# C210_0003_SARA_Module_220601.net
KiCad netlist of a schematic drawn in Altium Designer
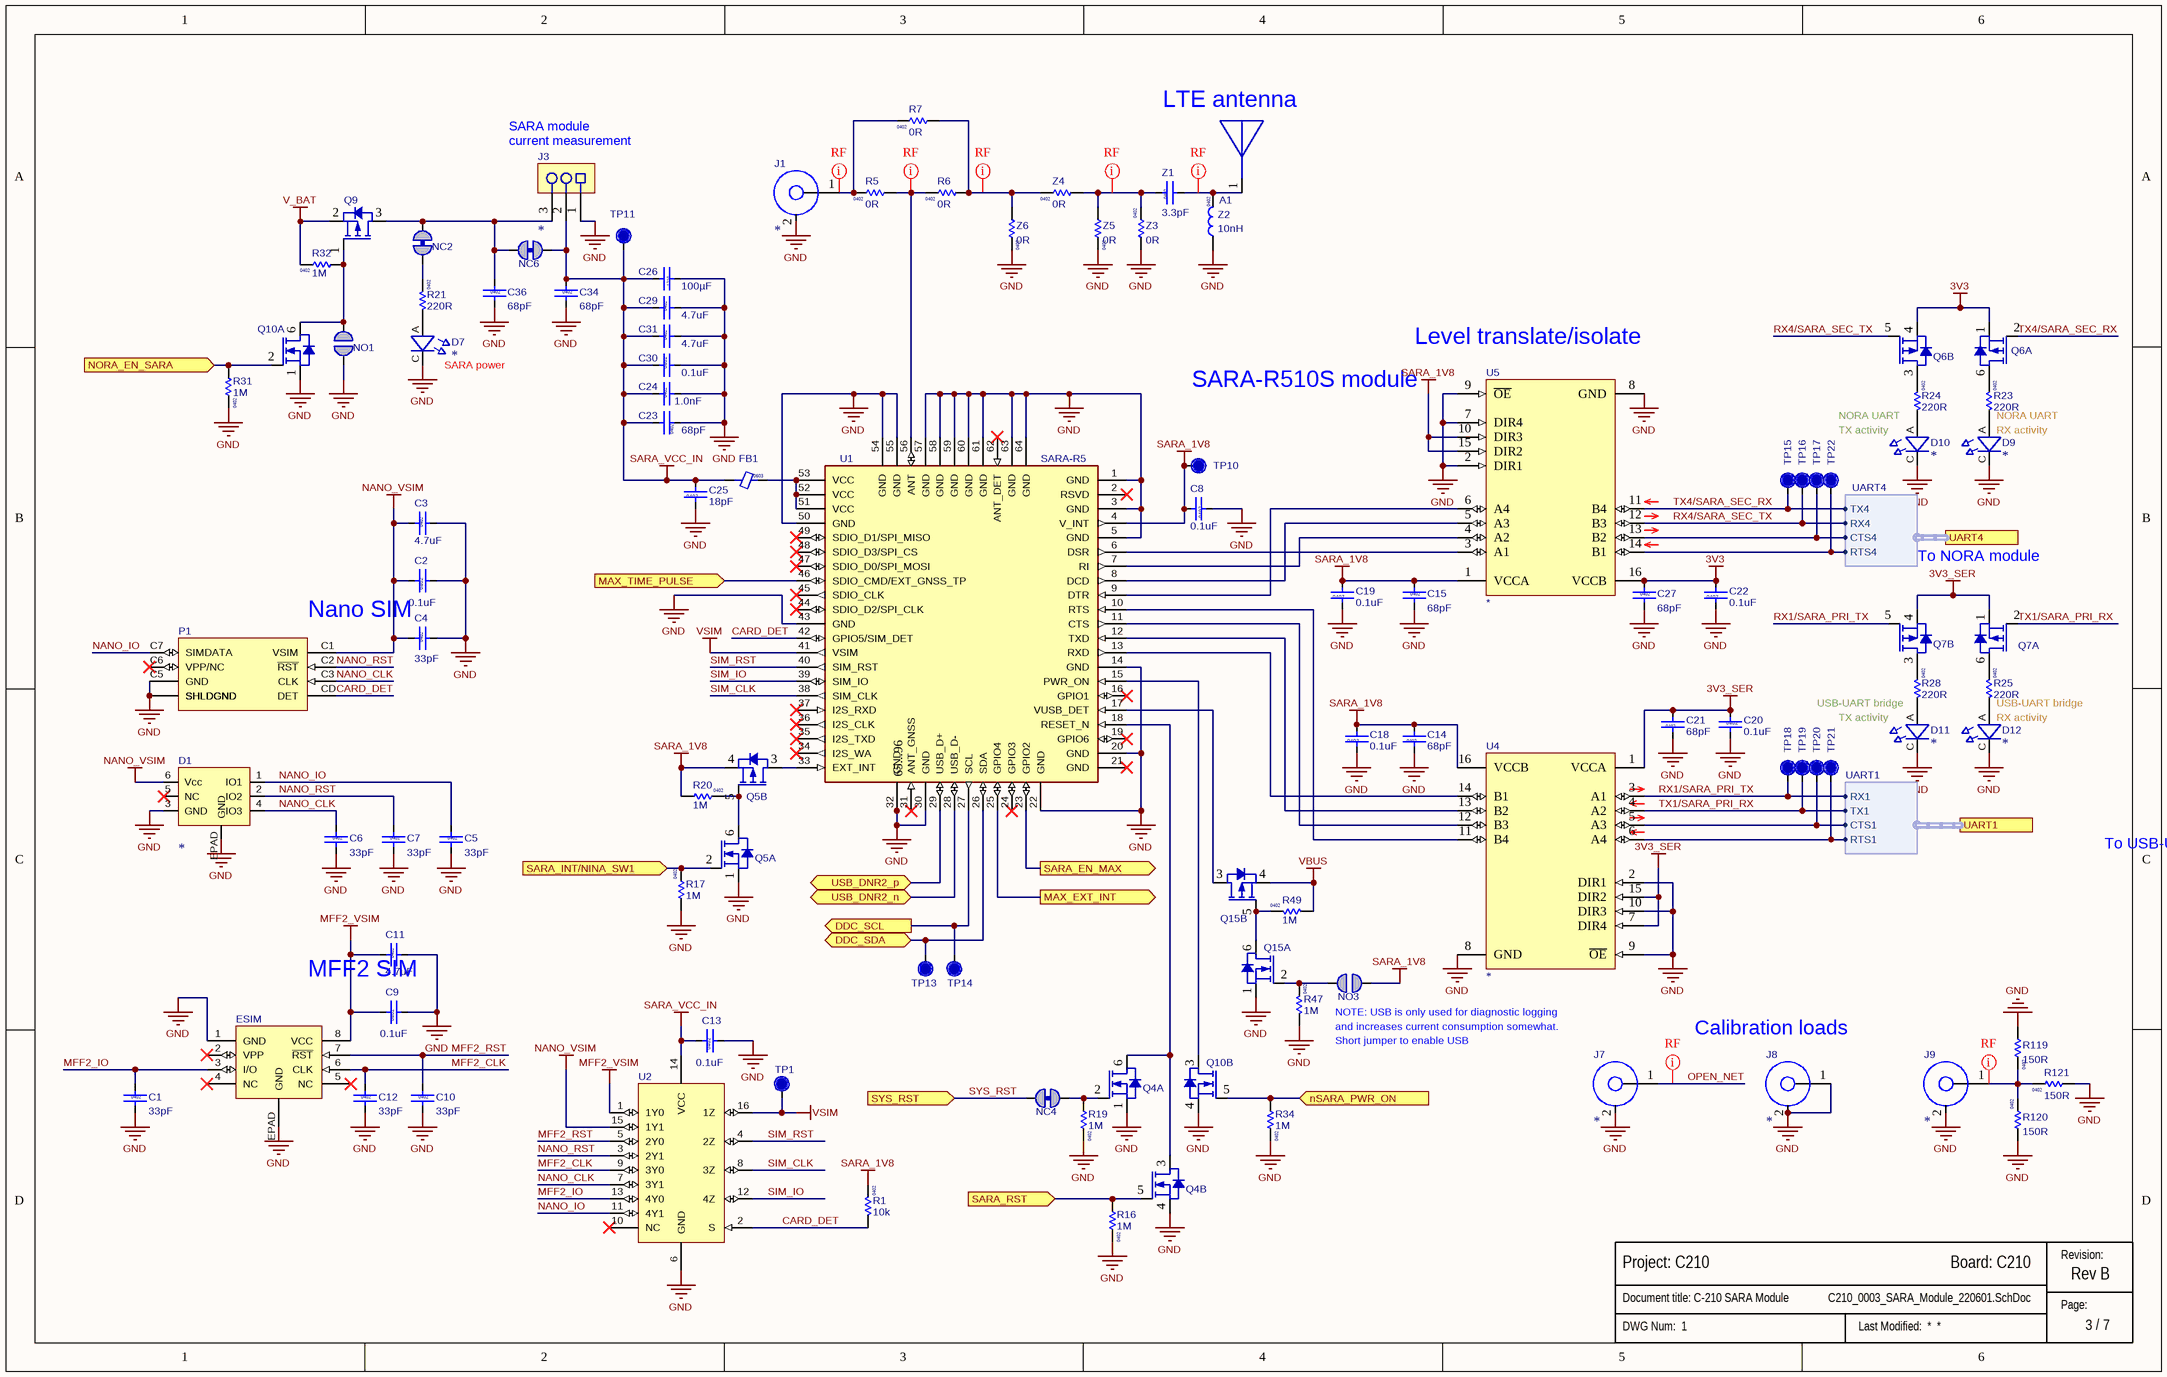
[diagram p0: C210_0003_SARA_Module_220601.SchDoc]

(export (version "E")
  (design (tool "Eeschema 10.0.6"))
  (components
    (comp (ref "A1")
      (value "PCS.66.A")
      (footprint "PCS_66_A")
      (description "RF Passive, Antenna, LTE, 600-6000MHz, Monopole")
      (fields (field (name "VOLTAGE") "None"))
      (libsource (lib "C210 Rev_B_220601") (part "PCS.66.A"))
    )
    (comp (ref "C1")
      (value "33pF")
      (footprint "Cap 0402 HD")
      (description "Cap, Ceramic,  33pF, 50V, 5%, NPO, 0402")
      (fields
        (field (name "SIZE") "0402")
        (field (name "PART NUMBER") "120-00045")
        (field (name "TOLERANCE") "+/- 5%")
      )
      (libsource (lib "Arena_Parts_DB_Lib") (part "Cap Chip"))
    )
    (comp (ref "C2")
      (value "0.1uF")
      (footprint "Cap 0402 HD")
      (description "Cap, Ceramic 0.1uF 10V 10% X5R 0402")
      (fields
        (field (name "SIZE") "0402")
        (field (name "PART NUMBER") "120-00016")
        (field (name "MANUFACTURER") "Murata Electronics North America")
      )
      (libsource (lib "Arena_Parts_DB_Lib") (part "Cap Chip"))
    )
    (comp (ref "C3")
      (value "4.7uF")
      (footprint "Cap 0402 HD")
      (description "Cap, Ceramic 4.7uF 10V 20% X5R 0402")
      (fields
        (field (name "SIZE") "0402")
        (field (name "PART NUMBER") "120-00020")
        (field (name "TOLERANCE") "+/- 20%")
      )
      (libsource (lib "Arena_Parts_DB_Lib") (part "Cap Chip"))
    )
    (comp (ref "C4")
      (value "33pF")
      (footprint "Cap 0402 HD")
      (description "Cap, Ceramic,  33pF, 50V, 5%, NPO, 0402")
      (fields
        (field (name "SIZE") "0402")
        (field (name "PART NUMBER") "120-00045")
        (field (name "TOLERANCE") "+/- 5%")
      )
      (libsource (lib "Arena_Parts_DB_Lib") (part "Cap Chip"))
    )
    (comp (ref "C5")
      (value "33pF")
      (footprint "Cap 0402 HD")
      (description "Cap, Ceramic,  33pF, 50V, 5%, NPO, 0402")
      (fields
        (field (name "SIZE") "0402")
        (field (name "PART NUMBER") "120-00045")
        (field (name "TOLERANCE") "+/- 5%")
      )
      (libsource (lib "Arena_Parts_DB_Lib") (part "Cap Chip"))
    )
    (comp (ref "C6")
      (value "33pF")
      (footprint "Cap 0402 HD")
      (description "Cap, Ceramic,  33pF, 50V, 5%, NPO, 0402")
      (fields
        (field (name "SIZE") "0402")
        (field (name "PART NUMBER") "120-00045")
        (field (name "TOLERANCE") "+/- 5%")
      )
      (libsource (lib "Arena_Parts_DB_Lib") (part "Cap Chip"))
    )
    (comp (ref "C7")
      (value "33pF")
      (footprint "Cap 0402 HD")
      (description "Cap, Ceramic,  33pF, 50V, 5%, NPO, 0402")
      (fields
        (field (name "SIZE") "0402")
        (field (name "PART NUMBER") "120-00045")
        (field (name "TOLERANCE") "+/- 5%")
      )
      (libsource (lib "Arena_Parts_DB_Lib") (part "Cap Chip"))
    )
    (comp (ref "C8")
      (value "0.1uF")
      (footprint "Cap 0402 HD")
      (description "Cap, Ceramic 0.1uF 10V 10% X5R 0402")
      (fields
        (field (name "SIZE") "0402")
        (field (name "PART NUMBER") "120-00016")
        (field (name "MANUFACTURER") "Murata Electronics North America")
      )
      (libsource (lib "Arena_Parts_DB_Lib") (part "Cap Chip"))
    )
    (comp (ref "C9")
      (value "0.1uF")
      (footprint "Cap 0402 HD")
      (description "Cap, Ceramic 0.1uF 10V 10% X5R 0402")
      (fields
        (field (name "SIZE") "0402")
        (field (name "PART NUMBER") "120-00016")
        (field (name "MANUFACTURER") "Murata Electronics North America")
      )
      (libsource (lib "Arena_Parts_DB_Lib") (part "Cap Chip"))
    )
    (comp (ref "C10")
      (value "33pF")
      (footprint "Cap 0402 HD")
      (description "Cap, Ceramic,  33pF, 50V, 5%, NPO, 0402")
      (fields
        (field (name "SIZE") "0402")
        (field (name "PART NUMBER") "120-00045")
        (field (name "TOLERANCE") "+/- 5%")
      )
      (libsource (lib "Arena_Parts_DB_Lib") (part "Cap Chip"))
    )
    (comp (ref "C11")
      (value "4.7uF")
      (footprint "Cap 0402 HD")
      (description "Cap, Ceramic 4.7uF 10V 20% X5R 0402")
      (fields
        (field (name "SIZE") "0402")
        (field (name "PART NUMBER") "120-00020")
        (field (name "TOLERANCE") "+/- 20%")
      )
      (libsource (lib "Arena_Parts_DB_Lib") (part "Cap Chip"))
    )
    (comp (ref "C12")
      (value "33pF")
      (footprint "Cap 0402 HD")
      (description "Cap, Ceramic,  33pF, 50V, 5%, NPO, 0402")
      (fields
        (field (name "SIZE") "0402")
        (field (name "PART NUMBER") "120-00045")
        (field (name "TOLERANCE") "+/- 5%")
      )
      (libsource (lib "Arena_Parts_DB_Lib") (part "Cap Chip"))
    )
    (comp (ref "C13")
      (value "0.1uF")
      (footprint "Cap 0402 HD")
      (description "Cap, Ceramic 0.1uF 10V 10% X5R 0402")
      (fields
        (field (name "SIZE") "0402")
        (field (name "PART NUMBER") "120-00016")
        (field (name "MANUFACTURER") "Murata Electronics North America")
      )
      (libsource (lib "Arena_Parts_DB_Lib") (part "Cap Chip"))
    )
    (comp (ref "C14")
      (value "68pF")
      (footprint "Cap 0402 HD")
      (description "Cap, Ceramic, 68pF, 50V, 1%, NP0, 0402")
      (fields
        (field (name "SIZE") "0402")
        (field (name "PART NUMBER") "120-00047")
        (field (name "TOLERANCE") "+/- 1%")
      )
      (libsource (lib "Arena_Parts_DB_Lib") (part "Cap Chip"))
    )
    (comp (ref "C15")
      (value "68pF")
      (footprint "Cap 0402 HD")
      (description "Cap, Ceramic, 68pF, 50V, 1%, NP0, 0402")
      (fields
        (field (name "SIZE") "0402")
        (field (name "PART NUMBER") "120-00047")
        (field (name "TOLERANCE") "+/- 1%")
      )
      (libsource (lib "Arena_Parts_DB_Lib") (part "Cap Chip"))
    )
    (comp (ref "C18")
      (value "0.1uF")
      (footprint "Cap 0402 HD")
      (description "Cap, Ceramic 0.1uF 10V 10% X5R 0402")
      (fields
        (field (name "SIZE") "0402")
        (field (name "PART NUMBER") "120-00016")
        (field (name "MANUFACTURER") "Murata Electronics North America")
      )
      (libsource (lib "Arena_Parts_DB_Lib") (part "Cap Chip"))
    )
    (comp (ref "C19")
      (value "0.1uF")
      (footprint "Cap 0402 HD")
      (description "Cap, Ceramic 0.1uF 10V 10% X5R 0402")
      (fields
        (field (name "SIZE") "0402")
        (field (name "PART NUMBER") "120-00016")
        (field (name "MANUFACTURER") "Murata Electronics North America")
      )
      (libsource (lib "Arena_Parts_DB_Lib") (part "Cap Chip"))
    )
    (comp (ref "C20")
      (value "0.1uF")
      (footprint "Cap 0402 HD")
      (description "Cap, Ceramic 0.1uF 10V 10% X5R 0402")
      (fields
        (field (name "SIZE") "0402")
        (field (name "PART NUMBER") "120-00016")
        (field (name "MANUFACTURER") "Murata Electronics North America")
      )
      (libsource (lib "Arena_Parts_DB_Lib") (part "Cap Chip"))
    )
    (comp (ref "C21")
      (value "68pF")
      (footprint "Cap 0402 HD")
      (description "Cap, Ceramic, 68pF, 50V, 1%, NP0, 0402")
      (fields
        (field (name "SIZE") "0402")
        (field (name "PART NUMBER") "120-00047")
        (field (name "TOLERANCE") "+/- 1%")
      )
      (libsource (lib "Arena_Parts_DB_Lib") (part "Cap Chip"))
    )
    (comp (ref "C22")
      (value "0.1uF")
      (footprint "Cap 0402 HD")
      (description "Cap, Ceramic 0.1uF 10V 10% X5R 0402")
      (fields
        (field (name "SIZE") "0402")
        (field (name "PART NUMBER") "120-00016")
        (field (name "MANUFACTURER") "Murata Electronics North America")
      )
      (libsource (lib "Arena_Parts_DB_Lib") (part "Cap Chip"))
    )
    (comp (ref "C23")
      (value "68pF")
      (footprint "Cap 0402 HD")
      (description "Cap, Ceramic, 68pF, 50V, 1%, NP0, 0402")
      (fields
        (field (name "SIZE") "0402")
        (field (name "PART NUMBER") "120-00047")
        (field (name "TOLERANCE") "+/- 1%")
      )
      (libsource (lib "Arena_Parts_DB_Lib") (part "Cap Chip"))
    )
    (comp (ref "C24")
      (value "1.0nF")
      (footprint "Cap 0402 HD")
      (description "CAP CER 1.0nF 50V 10% X7R 0402")
      (fields
        (field (name "SIZE") "0402")
        (field (name "PART NUMBER") "120-00010")
        (field (name "TOLERANCE") "+/- 10%")
      )
      (libsource (lib "Arena_Parts_DB_Lib") (part "Cap Chip"))
    )
    (comp (ref "C25")
      (value "18pF")
      (footprint "Cap 0402 HD")
      (description "Cap, Ceramic 18pF 50V 5% NP0 0402")
      (fields
        (field (name "SIZE") "0402")
        (field (name "PART NUMBER") "120-00041")
        (field (name "TOLERANCE") "+/- 5%")
      )
      (libsource (lib "Arena_Parts_DB_Lib") (part "Cap Chip"))
    )
    (comp (ref "C26")
      (value "100µF")
      (footprint "Cap 1210")
      (description "100µF ±20% 10V Ceramic Capacitor X5R 1210 (3225 Metric)")
      (fields
        (field (name "SIZE") "1210")
        (field (name "PART NUMBER") "120-00223")
        (field (name "TOLERANCE") "+/- 20%")
      )
      (libsource (lib "Arena_Parts_DB_Lib") (part "Cap Chip"))
    )
    (comp (ref "C27")
      (value "68pF")
      (footprint "Cap 0402 HD")
      (description "Cap, Ceramic, 68pF, 50V, 1%, NP0, 0402")
      (fields
        (field (name "SIZE") "0402")
        (field (name "PART NUMBER") "120-00047")
        (field (name "TOLERANCE") "+/- 1%")
      )
      (libsource (lib "Arena_Parts_DB_Lib") (part "Cap Chip"))
    )
    (comp (ref "C29")
      (value "4.7uF")
      (footprint "Cap 0402 HD")
      (description "Cap, Ceramic 4.7uF 10V 20% X5R 0402")
      (fields
        (field (name "SIZE") "0402")
        (field (name "PART NUMBER") "120-00020")
        (field (name "TOLERANCE") "+/- 20%")
      )
      (libsource (lib "Arena_Parts_DB_Lib") (part "Cap Chip"))
    )
    (comp (ref "C30")
      (value "0.1uF")
      (footprint "Cap 0402 HD")
      (description "Cap, Ceramic 0.1uF 10V 10% X5R 0402")
      (fields
        (field (name "SIZE") "0402")
        (field (name "PART NUMBER") "120-00016")
        (field (name "MANUFACTURER") "Murata Electronics North America")
      )
      (libsource (lib "Arena_Parts_DB_Lib") (part "Cap Chip"))
    )
    (comp (ref "C31")
      (value "4.7uF")
      (footprint "Cap 0402 HD")
      (description "Cap, Ceramic 4.7uF 10V 20% X5R 0402")
      (fields
        (field (name "SIZE") "0402")
        (field (name "PART NUMBER") "120-00020")
        (field (name "TOLERANCE") "+/- 20%")
      )
      (libsource (lib "Arena_Parts_DB_Lib") (part "Cap Chip"))
    )
    (comp (ref "C34")
      (value "68pF")
      (footprint "Cap 0402 HD")
      (description "Cap, Ceramic, 68pF, 50V, 1%, NP0, 0402")
      (fields
        (field (name "SIZE") "0402")
        (field (name "PART NUMBER") "120-00047")
        (field (name "TOLERANCE") "+/- 1%")
      )
      (libsource (lib "Arena_Parts_DB_Lib") (part "Cap Chip"))
    )
    (comp (ref "C36")
      (value "68pF")
      (footprint "Cap 0402 HD")
      (description "Cap, Ceramic, 68pF, 50V, 1%, NP0, 0402")
      (fields
        (field (name "SIZE") "0402")
        (field (name "PART NUMBER") "120-00047")
        (field (name "TOLERANCE") "+/- 1%")
      )
      (libsource (lib "Arena_Parts_DB_Lib") (part "Cap Chip"))
    )
    (comp (ref "D1")
      (value "~")
      (footprint "TPD3E001DRSR")
      (description "TVS Diode, ESD High Speed 3-Channel Array, WSON-6, 3mmX3mm")
      (fields (field (name "VOLTAGE") "5.5V") (field (name "MANUFACTURER P/N") "*"))
      (libsource (lib "TPD3E001DRSR") (part "TPD3E001"))
    )
    (comp (ref "D7")
      (value "LTST-C190EKT")
      (footprint "LTST-C190EKT")
      (description "DIODE, LED, SMT, Red, CLEAR LENS, 2.0V 10mA, 0603")
      (fields (field (name "VOLTAGE") "2.0V") (field (name "COLOR") "*"))
      (libsource (lib "LTST-C190EKT") (part "LTST-C190EKT"))
    )
    (comp (ref "D9")
      (value "LTST-C190YKT")
      (footprint "LTST-C190YKT")
      (description "DIODE, LED, SMT, YELLOW, CLEAR LENS, 2.1V 10mA, 0603")
      (fields (field (name "VOLTAGE") "2.1V") (field (name "COLOR") "*"))
      (libsource (lib "LTST-C190YKT") (part "LTST-C190YKT"))
    )
    (comp (ref "D10")
      (value "115-00019")
      (footprint "LTST-C190KGKT")
      (description "DIODE, LED, SMT, GREEN, CLEAR LENS, 2.0V 20mA, 0603")
      (fields (field (name "VOLTAGE") "2.0V") (field (name "COLOR") "*"))
      (libsource (lib "LTST-C190KGKT") (part "LTST-C190KGKT"))
    )
    (comp (ref "D11")
      (value "115-00019")
      (footprint "LTST-C190KGKT")
      (description "DIODE, LED, SMT, GREEN, CLEAR LENS, 2.0V 20mA, 0603")
      (fields (field (name "VOLTAGE") "2.0V") (field (name "COLOR") "*"))
      (libsource (lib "LTST-C190KGKT") (part "LTST-C190KGKT"))
    )
    (comp (ref "D12")
      (value "LTST-C190YKT")
      (footprint "LTST-C190YKT")
      (description "DIODE, LED, SMT, YELLOW, CLEAR LENS, 2.1V 10mA, 0603")
      (fields (field (name "VOLTAGE") "2.1V") (field (name "COLOR") "*"))
      (libsource (lib "LTST-C190YKT") (part "LTST-C190YKT"))
    )
    (comp (ref "ESIM")
      (value "MFF2 SIM")
      (footprint "MFF2 SIM")
      (description "ESIM, SMT, MFF2, 1.8V, SMT, VFDFPN8, 5mmX6mm")
      (fields (field (name "VOLTAGE") "1.8V"))
      (libsource (lib "MFF2") (part "MFF2 SIM"))
    )
    (comp (ref "FB1")
      (value "BLM18EG221SN1")
      (footprint "BLM18EG221SN1")
      (description "Ferrite Bead, 220ohm @ 100MHz, 2A, 0603")
      (fields (field (name "VOLTAGE") "None") (field (name "SIZE") "0603"))
      (libsource (lib "BLM18EG221SN1") (part "BLM18EG221SN1"))
    )
    (comp (ref "J1")
      (value "130-00067")
      (footprint "U.FL_3Pin")
      (description "U.FL jack, SMA 50 ohm, 3 pin, SMT")
      (fields (field (name "MANUFACTURER P/N") "*") (field (name "VOLTAGE") "None"))
      (libsource (lib "Arena_Parts_DB_Lib") (part "CON_Coax_2Pin"))
    )
    (comp (ref "J3")
      (value "130-00105")
      (footprint "HDR-0.1P-3Pin-1Row-SMT")
      (description "Header, 0.100\" Pitch, 3 Pin, Vertical SMT, Black")
      (fields (field (name "MANUFACTURER P/N") "*") (field (name "VOLTAGE") "None"))
      (libsource (lib "Arena_Parts_DB_Lib") (part "CON-3Pin_1Row"))
    )
    (comp (ref "J7")
      (value "130-00067")
      (footprint "U.FL_3Pin")
      (description "U.FL jack, SMA 50 ohm, 3 pin, SMT")
      (fields (field (name "MANUFACTURER P/N") "*") (field (name "VOLTAGE") "None"))
      (libsource (lib "Arena_Parts_DB_Lib") (part "CON_Coax_2Pin"))
    )
    (comp (ref "J8")
      (value "130-00067")
      (footprint "U.FL_3Pin")
      (description "U.FL jack, SMA 50 ohm, 3 pin, SMT")
      (fields (field (name "MANUFACTURER P/N") "*") (field (name "VOLTAGE") "None"))
      (libsource (lib "Arena_Parts_DB_Lib") (part "CON_Coax_2Pin"))
    )
    (comp (ref "J9")
      (value "130-00067")
      (footprint "U.FL_3Pin")
      (description "U.FL jack, SMA 50 ohm, 3 pin, SMT")
      (fields (field (name "MANUFACTURER P/N") "*") (field (name "VOLTAGE") "None"))
      (libsource (lib "Arena_Parts_DB_Lib") (part "CON_Coax_2Pin"))
    )
    (comp (ref "NC2")
      (value "Solderbridge-ShortDNP")
      (footprint "Solderbridge-Short")
      (description "Solderbridge-Short")
      (fields (field (name "ADDED BY") "Paul B"))
      (libsource (lib "PCB_Misc") (part "Solderbridge-Short"))
    )
    (comp (ref "NC4")
      (value "Solderbridge-ShortDNP")
      (footprint "Solderbridge-Short")
      (description "Solderbridge-Short")
      (fields (field (name "ADDED BY") "Paul B"))
      (libsource (lib "") (part "Solderbridge-Short_1"))
    )
    (comp (ref "NC6")
      (value "Solderbridge-ShortDNP")
      (footprint "Solderbridge-Short")
      (description "Solderbridge-Short")
      (fields (field (name "ADDED BY") "Paul B"))
      (libsource (lib "") (part "Solderbridge-Short_1"))
    )
    (comp (ref "NO1")
      (value "Solderbridge-OpenDNP")
      (footprint "Solderbridge-Open")
      (description "Solderbridge-Open")
      (fields (field (name "ADDED BY") "Paul B"))
      (libsource (lib "PCB_Misc") (part "Solderbridge-Open"))
    )
    (comp (ref "NO3")
      (value "Solderbridge-OpenDNP")
      (footprint "Solderbridge-Open")
      (description "Solderbridge-Open")
      (fields (field (name "ADDED BY") "Paul B"))
      (libsource (lib "PCB_Misc") (part "Solderbridge-Open"))
    )
    (comp (ref "P1")
      (value "SIM8065")
      (footprint "SIM6065-6-1-14-01-A")
      (description "NANO SIM SOCKET, SWITCH, SMT, PUSH-PUSH, 13mmX14mm")
      (fields (field (name "VOLTAGE") "30V"))
      (libsource (lib "SIM8065-6-1-14-01-A") (part "SIM8065"))
    )
    (comp (ref "Q4")
      (value "140-00016")
      (footprint "SOT-563")
      (description "MOSFET 2N-CH 20V 0.8A, SOT-563")
      (fields (field (name "VOLTAGE") "20V"))
      (libsource (lib "Arena_Parts_DB_Lib") (part "MOSFET-N-Dual"))
    )
    (comp (ref "Q5")
      (value "140-00030")
      (footprint "SOT-563")
      (description "MOSFET N/P-CH 20V SOT-563, 540 mA, −430 mA")
      (fields (field (name "VOLTAGE") "20V"))
      (libsource (lib "Arena_Parts_DB_Lib") (part "MOSFET-N-P_Pair"))
    )
    (comp (ref "Q6")
      (value "FDY2000PZ")
      (footprint "FDY2000PZ")
      (description "MOSFET DUAL P-CH 20V SOT-563, -350mA")
      (fields (field (name "VOLTAGE") "20V"))
      (libsource (lib "FDY2000PZ") (part "MOSFET-Dual-P_Chan"))
    )
    (comp (ref "Q7")
      (value "FDY2000PZ")
      (footprint "FDY2000PZ")
      (description "MOSFET DUAL P-CH 20V SOT-563, -350mA")
      (fields (field (name "VOLTAGE") "20V"))
      (libsource (lib "FDY2000PZ") (part "MOSFET-Dual-P_Chan"))
    )
    (comp (ref "Q9")
      (value "140-00008")
      (footprint "SOT-23")
      (description "P-MOSFET, 20V 3.1A, SOT-23")
      (fields (field (name "VOLTAGE") "20V"))
      (libsource (lib "Arena_Parts_DB_Lib") (part "MOSFET-P"))
    )
    (comp (ref "Q10")
      (value "140-00016")
      (footprint "SOT-563")
      (description "MOSFET 2N-CH 20V 0.8A, SOT-563")
      (fields (field (name "VOLTAGE") "20V"))
      (libsource (lib "Arena_Parts_DB_Lib") (part "MOSFET-N-Dual"))
    )
    (comp (ref "Q15")
      (value "140-00030")
      (footprint "SOT-563")
      (description "MOSFET N/P-CH 20V SOT-563, 540 mA, −430 mA")
      (fields (field (name "VOLTAGE") "20V"))
      (libsource (lib "Arena_Parts_DB_Lib") (part "MOSFET-N-P_Pair"))
    )
    (comp (ref "R1")
      (value "10k")
      (footprint "RES 0402 HD")
      (description "Resistor 10k ohm 1% 1/16W, 0402")
      (fields
        (field (name "SIZE") "0402")
        (field (name "PART NUMBER") "180-00024")
        (field (name "POWER") "1/16W")
      )
      (libsource (lib "Arena_Parts_DB_Lib") (part "Res sm"))
    )
    (comp (ref "R5")
      (value "0R")
      (footprint "RES 0402 HD")
      (description "Resistor 0 ohm 1/16W 0402")
      (fields
        (field (name "SIZE") "0402")
        (field (name "PART NUMBER") "180-00020")
        (field (name "POWER") "1/16W")
      )
      (libsource (lib "Arena_Parts_DB_Lib") (part "Res sm"))
    )
    (comp (ref "R6")
      (value "0R")
      (footprint "RES 0402 HD")
      (description "Resistor 0 ohm 1/16W 0402")
      (fields
        (field (name "SIZE") "0402")
        (field (name "PART NUMBER") "180-00020")
        (field (name "POWER") "1/16W")
      )
      (libsource (lib "Arena_Parts_DB_Lib") (part "Res sm"))
    )
    (comp (ref "R7")
      (value "0R")
      (footprint "RES 0402 HD")
      (description "Resistor 0 ohm 1/16W 0402")
      (fields
        (field (name "SIZE") "0402")
        (field (name "PART NUMBER") "180-00020")
        (field (name "POWER") "1/16W")
      )
      (libsource (lib "Arena_Parts_DB_Lib") (part "Res sm"))
    )
    (comp (ref "R16")
      (value "1M")
      (footprint "RES 0402 HD")
      (description "Resistor 1M ohm 1%, 1/16W, 0402")
      (fields
        (field (name "SIZE") "0402")
        (field (name "PART NUMBER") "180-00054")
        (field (name "POWER") "1/16W")
      )
      (libsource (lib "Arena_Parts_DB_Lib") (part "Res sm"))
    )
    (comp (ref "R17")
      (value "1M")
      (footprint "RES 0402 HD")
      (description "Resistor 1M ohm 1%, 1/16W, 0402")
      (fields
        (field (name "SIZE") "0402")
        (field (name "PART NUMBER") "180-00054")
        (field (name "POWER") "1/16W")
      )
      (libsource (lib "Arena_Parts_DB_Lib") (part "Res sm"))
    )
    (comp (ref "R19")
      (value "1M")
      (footprint "RES 0402 HD")
      (description "Resistor 1M ohm 1%, 1/16W, 0402")
      (fields
        (field (name "SIZE") "0402")
        (field (name "PART NUMBER") "180-00054")
        (field (name "POWER") "1/16W")
      )
      (libsource (lib "Arena_Parts_DB_Lib") (part "Res sm"))
    )
    (comp (ref "R20")
      (value "1M")
      (footprint "RES 0402 HD")
      (description "Resistor 1M ohm 1%, 1/16W, 0402")
      (fields
        (field (name "SIZE") "0402")
        (field (name "PART NUMBER") "180-00054")
        (field (name "POWER") "1/16W")
      )
      (libsource (lib "Arena_Parts_DB_Lib") (part "Res sm"))
    )
    (comp (ref "R21")
      (value "220R")
      (footprint "RES 0402 HD")
      (description "Resistor, 220ohm, 5%, 1/16W, 0402.")
      (fields
        (field (name "SIZE") "0402")
        (field (name "PART NUMBER") "180-00098")
        (field (name "MANUFACTURER") "Panasonic Electronic Components")
      )
      (libsource (lib "Arena_Parts_DB_Lib") (part "Res sm"))
    )
    (comp (ref "R23")
      (value "220R")
      (footprint "RES 0402 HD")
      (description "Resistor, 220ohm, 5%, 1/16W, 0402.")
      (fields
        (field (name "SIZE") "0402")
        (field (name "PART NUMBER") "180-00098")
        (field (name "MANUFACTURER") "Panasonic Electronic Components")
      )
      (libsource (lib "Arena_Parts_DB_Lib") (part "Res sm"))
    )
    (comp (ref "R24")
      (value "220R")
      (footprint "RES 0402 HD")
      (description "Resistor, 220ohm, 5%, 1/16W, 0402.")
      (fields
        (field (name "SIZE") "0402")
        (field (name "PART NUMBER") "180-00098")
        (field (name "MANUFACTURER") "Panasonic Electronic Components")
      )
      (libsource (lib "Arena_Parts_DB_Lib") (part "Res sm"))
    )
    (comp (ref "R25")
      (value "220R")
      (footprint "RES 0402 HD")
      (description "Resistor, 220ohm, 5%, 1/16W, 0402.")
      (fields
        (field (name "SIZE") "0402")
        (field (name "PART NUMBER") "180-00098")
        (field (name "MANUFACTURER") "Panasonic Electronic Components")
      )
      (libsource (lib "Arena_Parts_DB_Lib") (part "Res sm"))
    )
    (comp (ref "R28")
      (value "220R")
      (footprint "RES 0402 HD")
      (description "Resistor, 220ohm, 5%, 1/16W, 0402.")
      (fields
        (field (name "SIZE") "0402")
        (field (name "PART NUMBER") "180-00098")
        (field (name "MANUFACTURER") "Panasonic Electronic Components")
      )
      (libsource (lib "Arena_Parts_DB_Lib") (part "Res sm"))
    )
    (comp (ref "R31")
      (value "1M")
      (footprint "RES 0402 HD")
      (description "Resistor 1M ohm 1%, 1/16W, 0402")
      (fields
        (field (name "SIZE") "0402")
        (field (name "PART NUMBER") "180-00054")
        (field (name "POWER") "1/16W")
      )
      (libsource (lib "Arena_Parts_DB_Lib") (part "Res sm"))
    )
    (comp (ref "R32")
      (value "1M")
      (footprint "RES 0402 HD")
      (description "Resistor 1M ohm 1%, 1/16W, 0402")
      (fields
        (field (name "SIZE") "0402")
        (field (name "PART NUMBER") "180-00054")
        (field (name "POWER") "1/16W")
      )
      (libsource (lib "Arena_Parts_DB_Lib") (part "Res sm"))
    )
    (comp (ref "R34")
      (value "1M")
      (footprint "RES 0402 HD")
      (description "Resistor 1M ohm 1%, 1/16W, 0402")
      (fields
        (field (name "SIZE") "0402")
        (field (name "PART NUMBER") "180-00054")
        (field (name "POWER") "1/16W")
      )
      (libsource (lib "Arena_Parts_DB_Lib") (part "Res sm"))
    )
    (comp (ref "R47")
      (value "1M")
      (footprint "RES 0402 HD")
      (description "Resistor 1M ohm 1%, 1/16W, 0402")
      (fields
        (field (name "SIZE") "0402")
        (field (name "PART NUMBER") "180-00054")
        (field (name "POWER") "1/16W")
      )
      (libsource (lib "Arena_Parts_DB_Lib") (part "Res sm"))
    )
    (comp (ref "R49")
      (value "1M")
      (footprint "RES 0402 HD")
      (description "Resistor 1M ohm 1%, 1/16W, 0402")
      (fields
        (field (name "SIZE") "0402")
        (field (name "PART NUMBER") "180-00054")
        (field (name "POWER") "1/16W")
      )
      (libsource (lib "Arena_Parts_DB_Lib") (part "Res sm"))
    )
    (comp (ref "R119")
      (value "150R")
      (footprint "RES 0402 HD")
      (description "RES SMD 150 OHM 1% 1/16W 0402")
      (fields
        (field (name "SIZE") "0402")
        (field (name "PART NUMBER") "180-00144")
        (field (name "POWER") "1/16W")
      )
      (libsource (lib "Arena_Parts_DB_Lib") (part "Res sm"))
    )
    (comp (ref "R120")
      (value "150R")
      (footprint "RES 0402 HD")
      (description "RES SMD 150 OHM 1% 1/16W 0402")
      (fields
        (field (name "SIZE") "0402")
        (field (name "PART NUMBER") "180-00144")
        (field (name "POWER") "1/16W")
      )
      (libsource (lib "Arena_Parts_DB_Lib") (part "Res sm"))
    )
    (comp (ref "R121")
      (value "150R")
      (footprint "RES 0402 HD")
      (description "RES SMD 150 OHM 1% 1/16W 0402")
      (fields
        (field (name "SIZE") "0402")
        (field (name "PART NUMBER") "180-00144")
        (field (name "POWER") "1/16W")
      )
      (libsource (lib "Arena_Parts_DB_Lib") (part "Res sm"))
    )
    (comp (ref "TP1")
      (value "TP")
      (footprint "TP12R")
      (description "Testpoint, Round 1.0mm Dia")
      (fields
        (field (name "PART NUMBER") "TP10R")
        (field (name "ADDED BY") "Jeremy D")
        (field (name "CHECKED BY") "Paul B")
      )
      (libsource (lib "PCB_Misc") (part "TP_R"))
    )
    (comp (ref "TP10")
      (value "TP")
      (footprint "TP12R")
      (description "Testpoint, Round 1.0mm Dia")
      (fields
        (field (name "PART NUMBER") "TP10R")
        (field (name "ADDED BY") "Jeremy D")
        (field (name "CHECKED BY") "Paul B")
      )
      (libsource (lib "PCB_Misc") (part "TP_R"))
    )
    (comp (ref "TP11")
      (value "TP")
      (footprint "TP12R")
      (description "Testpoint, Round 1.0mm Dia")
      (fields
        (field (name "PART NUMBER") "TP10R")
        (field (name "ADDED BY") "Jeremy D")
        (field (name "CHECKED BY") "Paul B")
      )
      (libsource (lib "PCB_Misc") (part "TP_R"))
    )
    (comp (ref "TP13")
      (value "TP")
      (footprint "TP12R")
      (description "Testpoint, Round 1.0mm Dia")
      (fields
        (field (name "PART NUMBER") "TP10R")
        (field (name "ADDED BY") "Jeremy D")
        (field (name "CHECKED BY") "Paul B")
      )
      (libsource (lib "PCB_Misc") (part "TP_R"))
    )
    (comp (ref "TP14")
      (value "TP")
      (footprint "TP12R")
      (description "Testpoint, Round 1.0mm Dia")
      (fields
        (field (name "PART NUMBER") "TP10R")
        (field (name "ADDED BY") "Jeremy D")
        (field (name "CHECKED BY") "Paul B")
      )
      (libsource (lib "PCB_Misc") (part "TP_R"))
    )
    (comp (ref "TP15")
      (value "TP")
      (footprint "TP12R")
      (description "Testpoint, Round 1.0mm Dia")
      (fields
        (field (name "PART NUMBER") "TP10R")
        (field (name "ADDED BY") "Jeremy D")
        (field (name "CHECKED BY") "Paul B")
      )
      (libsource (lib "PCB_Misc") (part "TP_R"))
    )
    (comp (ref "TP16")
      (value "TP")
      (footprint "TP12R")
      (description "Testpoint, Round 1.0mm Dia")
      (fields
        (field (name "PART NUMBER") "TP10R")
        (field (name "ADDED BY") "Jeremy D")
        (field (name "CHECKED BY") "Paul B")
      )
      (libsource (lib "PCB_Misc") (part "TP_R"))
    )
    (comp (ref "TP17")
      (value "TP")
      (footprint "TP12R")
      (description "Testpoint, Round 1.0mm Dia")
      (fields
        (field (name "PART NUMBER") "TP10R")
        (field (name "ADDED BY") "Jeremy D")
        (field (name "CHECKED BY") "Paul B")
      )
      (libsource (lib "PCB_Misc") (part "TP_R"))
    )
    (comp (ref "TP18")
      (value "TP")
      (footprint "TP12R")
      (description "Testpoint, Round 1.0mm Dia")
      (fields
        (field (name "PART NUMBER") "TP10R")
        (field (name "ADDED BY") "Jeremy D")
        (field (name "CHECKED BY") "Paul B")
      )
      (libsource (lib "PCB_Misc") (part "TP_R"))
    )
    (comp (ref "TP19")
      (value "TP")
      (footprint "TP12R")
      (description "Testpoint, Round 1.0mm Dia")
      (fields
        (field (name "PART NUMBER") "TP10R")
        (field (name "ADDED BY") "Jeremy D")
        (field (name "CHECKED BY") "Paul B")
      )
      (libsource (lib "PCB_Misc") (part "TP_R"))
    )
    (comp (ref "TP20")
      (value "TP")
      (footprint "TP12R")
      (description "Testpoint, Round 1.0mm Dia")
      (fields
        (field (name "PART NUMBER") "TP10R")
        (field (name "ADDED BY") "Jeremy D")
        (field (name "CHECKED BY") "Paul B")
      )
      (libsource (lib "PCB_Misc") (part "TP_R"))
    )
    (comp (ref "TP21")
      (value "TP")
      (footprint "TP12R")
      (description "Testpoint, Round 1.0mm Dia")
      (fields
        (field (name "PART NUMBER") "TP10R")
        (field (name "ADDED BY") "Jeremy D")
        (field (name "CHECKED BY") "Paul B")
      )
      (libsource (lib "PCB_Misc") (part "TP_R"))
    )
    (comp (ref "TP22")
      (value "TP")
      (footprint "TP12R")
      (description "Testpoint, Round 1.0mm Dia")
      (fields
        (field (name "PART NUMBER") "TP10R")
        (field (name "ADDED BY") "Jeremy D")
        (field (name "CHECKED BY") "Paul B")
      )
      (libsource (lib "PCB_Misc") (part "TP_R"))
    )
    (comp (ref "U1")
      (value "SARA-R5")
      (footprint "SARA-XX")
      (description "GSM/GPRS and GSM/EGPRS/HSPA Cellular Module")
      (fields (field (name "MANUFACTURER") "u-blox"))
      (libsource (lib "ubloxLib") (part "SARA-R5"))
    )
    (comp (ref "U2")
      (value "NX3DV2567")
      (footprint "XQFN-16")
      (description "IC, ANLG SWITCH, 4PDT, SIM OPTIMIZED, 1.4V-4.3V, SMT, XQFN-16, 2.6mmX1.8mm")
      (fields (field (name "VOLTAGE") "1.4V-4.3V"))
      (libsource (lib "NX3DV2567") (part "NX3DV2567"))
    )
    (comp (ref "U4")
      (value "225-00011")
      (footprint "QFN0.5P2x6-16Pin_W-Pad")
      (description "Voltage Level Translator Bidirectional 1 Circuit 4 Channel 380Mbps 16-DHVQFN (2.5x3.5)")
      (fields (field (name "MANUFACTURER P/N") "*") (field (name "VOLTAGE") "3.6V"))
      (libsource (lib "") (part "74AVC4TD245_1"))
    )
    (comp (ref "U5")
      (value "225-00011")
      (footprint "QFN0.5P2x6-16Pin_W-Pad")
      (description "Voltage Level Translator Bidirectional 1 Circuit 4 Channel 380Mbps 16-DHVQFN (2.5x3.5)")
      (fields (field (name "MANUFACTURER P/N") "*") (field (name "VOLTAGE") "3.6V"))
      (libsource (lib "Arena_Parts_DB_Lib") (part "74AVC4TD245"))
    )
    (comp (ref "Z1")
      (value "3.3pF")
      (footprint "Cap 0402 HD")
      (description "CAP CER 3.3PF 50V +/-0.25pF NP0 0402")
      (fields
        (field (name "SIZE") "0402")
        (field (name "PART NUMBER") "120-00079")
        (field (name "TOLERANCE") "Other")
      )
      (libsource (lib "Arena_Parts_DB_Lib") (part "Cap Chip"))
    )
    (comp (ref "Z2")
      (value "10nH")
      (footprint "IND 0402")
      (description "INDUCTOR 10NH 300MA 0402")
      (fields
        (field (name "SIZE") "0402")
        (field (name "PART NUMBER") "150-00010")
        (field (name "TOLERANCE") "+/- 5%")
      )
      (libsource (lib "Arena_Parts_DB_Lib") (part "Ind sm"))
    )
    (comp (ref "Z3")
      (value "0R")
      (footprint "RES 0402 HD")
      (description "Resistor 0 ohm 1/16W 0402")
      (fields
        (field (name "SIZE") "0402")
        (field (name "PART NUMBER") "180-00020")
        (field (name "POWER") "1/16W")
      )
      (libsource (lib "Arena_Parts_DB_Lib") (part "Res sm"))
    )
    (comp (ref "Z4")
      (value "0R")
      (footprint "RES 0402 HD")
      (description "Resistor 0 ohm 1/16W 0402")
      (fields
        (field (name "SIZE") "0402")
        (field (name "PART NUMBER") "180-00020")
        (field (name "POWER") "1/16W")
      )
      (libsource (lib "Arena_Parts_DB_Lib") (part "Res sm"))
    )
    (comp (ref "Z5")
      (value "0R")
      (footprint "RES 0402 HD")
      (description "Resistor 0 ohm 1/16W 0402")
      (fields
        (field (name "SIZE") "0402")
        (field (name "PART NUMBER") "180-00020")
        (field (name "POWER") "1/16W")
      )
      (libsource (lib "Arena_Parts_DB_Lib") (part "Res sm"))
    )
    (comp (ref "Z6")
      (value "0R")
      (footprint "RES 0402 HD")
      (description "Resistor 0 ohm 1/16W 0402")
      (fields
        (field (name "SIZE") "0402")
        (field (name "PART NUMBER") "180-00020")
        (field (name "POWER") "1/16W")
      )
      (libsource (lib "Arena_Parts_DB_Lib") (part "Res sm"))
    )
  )
  (nets
    (net (code "3") (name "/CARD_DET") (class "Default")
      (node (ref "P1") (pin "CD") (pinfunction "DET_CD") (pintype "passive"))
      (node (ref "R1") (pin "1") (pinfunction "1_1") (pintype "passive"))
      (node (ref "U1") (pin "42") (pinfunction "GPIO5/SIM_DET_42") (pintype "bidirectional"))
      (node (ref "U2") (pin "2") (pinfunction "S_2") (pintype "input"))
    )
    (net (code "4") (name "/DDC_SCL") (class "Default")
      (node (ref "TP14") (pin "1") (pintype "passive"))
      (node (ref "U1") (pin "27") (pinfunction "SCL_27") (pintype "output"))
    )
    (net (code "5") (name "/DDC_SDA") (class "Default")
      (node (ref "TP13") (pin "1") (pintype "passive"))
      (node (ref "U1") (pin "26") (pinfunction "SDA_26") (pintype "bidirectional"))
    )
    (net (code "6") (name "/MAX_EXT_INT") (class "Default")
      (node (ref "U1") (pin "25") (pinfunction "GPIO4_25") (pintype "bidirectional"))
    )
    (net (code "7") (name "/MAX_TIME_PULSE") (class "Default")
      (node (ref "U1") (pin "46") (pinfunction "SDIO_CMD/EXT_GNSS_TP_46") (pintype "bidirectional"))
    )
    (net (code "8") (name "/MFF2_CLK") (class "Default")
      (node (ref "C12") (pin "1") (pinfunction "1_1") (pintype "passive"))
      (node (ref "ESIM") (pin "6") (pinfunction "CLK_6") (pintype "input"))
      (node (ref "U2") (pin "9") (pinfunction "3Y0_9") (pintype "bidirectional"))
    )
    (net (code "9") (name "/MFF2_IO") (class "Default")
      (node (ref "C1") (pin "1") (pinfunction "1_1") (pintype "passive"))
      (node (ref "ESIM") (pin "3") (pinfunction "I/O_3") (pintype "bidirectional"))
      (node (ref "U2") (pin "13") (pinfunction "4Y0_13") (pintype "bidirectional"))
    )
    (net (code "10") (name "/MFF2_RST") (class "Default")
      (node (ref "C10") (pin "1") (pinfunction "1_1") (pintype "passive"))
      (node (ref "ESIM") (pin "7") (pinfunction "~{RST}_7") (pintype "input"))
      (node (ref "U2") (pin "5") (pinfunction "2Y0_5") (pintype "bidirectional"))
    )
    (net (code "11") (name "/NANO_CLK") (class "Default")
      (node (ref "C6") (pin "1") (pinfunction "1_1") (pintype "passive"))
      (node (ref "D1") (pin "4") (pinfunction "IO3_4") (pintype "passive"))
      (node (ref "P1") (pin "C3") (pinfunction "CLK_C3") (pintype "input"))
      (node (ref "U2") (pin "7") (pinfunction "3Y1_7") (pintype "bidirectional"))
    )
    (net (code "12") (name "/NANO_IO") (class "Default")
      (node (ref "C5") (pin "1") (pinfunction "1_1") (pintype "passive"))
      (node (ref "D1") (pin "1") (pinfunction "IO1_1") (pintype "passive"))
      (node (ref "P1") (pin "C7") (pinfunction "SIMDATA_C7") (pintype "bidirectional"))
      (node (ref "U2") (pin "11") (pinfunction "4Y1_11") (pintype "bidirectional"))
    )
    (net (code "13") (name "/NANO_RST") (class "Default")
      (node (ref "C7") (pin "1") (pinfunction "1_1") (pintype "passive"))
      (node (ref "D1") (pin "2") (pinfunction "IO2_2") (pintype "passive"))
      (node (ref "P1") (pin "C2") (pinfunction "~{RST}_C2") (pintype "input"))
      (node (ref "U2") (pin "3") (pinfunction "2Y1_3") (pintype "bidirectional"))
    )
    (net (code "14") (name "/NORA_EN_SARA") (class "Default")
      (node (ref "Q10") (pin "2") (pinfunction "G1_2") (pintype "passive"))
      (node (ref "R31") (pin "1") (pinfunction "1_1") (pintype "passive"))
    )
    (net (code "15") (name "/OPEN_NET") (class "Default")
      (node (ref "J7") (pin "1") (pinfunction "ANT_1") (pintype "passive"))
    )
    (net (code "16") (name "/RX1{slash}SARA_PRI_TX") (class "Default")
      (node (ref "Q7") (pin "5") (pinfunction "G2_5") (pintype "passive"))
      (node (ref "TP18") (pin "1") (pintype "passive"))
      (node (ref "U4") (pin "3") (pinfunction "A1_3") (pintype "bidirectional"))
    )
    (net (code "17") (name "/RX4{slash}SARA_SEC_TX") (class "Default")
      (node (ref "Q6") (pin "5") (pinfunction "G2_5") (pintype "passive"))
      (node (ref "TP16") (pin "1") (pintype "passive"))
      (node (ref "U5") (pin "12") (pinfunction "B3_12") (pintype "bidirectional"))
    )
    (net (code "18") (name "/SARA_EN_MAX") (class "Default")
      (node (ref "U1") (pin "23") (pinfunction "GPIO2_23") (pintype "bidirectional"))
    )
    (net (code "19") (name "/SARA_INT{slash}NINA_SW1") (class "Default")
      (node (ref "Q5") (pin "2") (pinfunction "G1_2") (pintype "passive"))
      (node (ref "R17") (pin "2") (pinfunction "2_2") (pintype "passive"))
    )
    (net (code "20") (name "/SARA_RST") (class "Default")
      (node (ref "Q4") (pin "5") (pinfunction "G2_5") (pintype "passive"))
      (node (ref "R16") (pin "1") (pinfunction "1_1") (pintype "passive"))
    )
    (net (code "21") (name "/SIM_CLK") (class "Default")
      (node (ref "U1") (pin "38") (pinfunction "SIM_CLK_38") (pintype "output"))
      (node (ref "U2") (pin "8") (pinfunction "3Z_8") (pintype "bidirectional"))
    )
    (net (code "22") (name "/SIM_IO") (class "Default")
      (node (ref "U1") (pin "39") (pinfunction "SIM_IO_39") (pintype "bidirectional"))
      (node (ref "U2") (pin "12") (pinfunction "4Z_12") (pintype "bidirectional"))
    )
    (net (code "23") (name "/SIM_RST") (class "Default")
      (node (ref "U1") (pin "40") (pinfunction "SIM_RST_40") (pintype "output"))
      (node (ref "U2") (pin "4") (pinfunction "2Z_4") (pintype "bidirectional"))
    )
    (net (code "24") (name "/SYS_RST") (class "Default")
      (node (ref "NC4") (pin "2") (pinfunction "2_2") (pintype "passive"))
    )
    (net (code "25") (name "/TX1{slash}SARA_PRI_RX") (class "Default")
      (node (ref "Q7") (pin "2") (pinfunction "G1_2") (pintype "passive"))
      (node (ref "TP19") (pin "1") (pintype "passive"))
      (node (ref "U4") (pin "4") (pinfunction "A2_4") (pintype "bidirectional"))
    )
    (net (code "26") (name "/TX4{slash}SARA_SEC_RX") (class "Default")
      (node (ref "Q6") (pin "2") (pinfunction "G1_2") (pintype "passive"))
      (node (ref "TP15") (pin "1") (pintype "passive"))
      (node (ref "U5") (pin "11") (pinfunction "B4_11") (pintype "bidirectional"))
    )
    (net (code "27") (name "/USB_DNR2_n") (class "Default")
      (node (ref "U1") (pin "28") (pinfunction "USB_D-_28") (pintype "bidirectional"))
    )
    (net (code "28") (name "/USB_DNR2_p") (class "Default")
      (node (ref "U1") (pin "29") (pinfunction "USB_D+_29") (pintype "bidirectional"))
    )
    (net (code "29") (name "/nSARA_PWR_ON") (class "Default")
      (node (ref "Q10") (pin "5") (pinfunction "G2_5") (pintype "passive"))
      (node (ref "R34") (pin "1") (pinfunction "1_1") (pintype "passive"))
    )
    (net (code "32") (name "3V3") (class "Default")
      (node (ref "C22") (pin "2") (pinfunction "2_2") (pintype "passive"))
      (node (ref "C27") (pin "1") (pinfunction "1_1") (pintype "passive"))
      (node (ref "Q6") (pin "1") (pinfunction "S1_1") (pintype "passive"))
      (node (ref "Q6") (pin "4") (pinfunction "S2_4") (pintype "passive"))
      (node (ref "U5") (pin "16") (pinfunction "VCCB_16") (pintype "power_in"))
    )
    (net (code "33") (name "3V3_SER") (class "Default")
      (node (ref "C20") (pin "1") (pinfunction "1_1") (pintype "passive"))
      (node (ref "C21") (pin "2") (pinfunction "2_2") (pintype "passive"))
      (node (ref "Q7") (pin "1") (pinfunction "S1_1") (pintype "passive"))
      (node (ref "Q7") (pin "4") (pinfunction "S2_4") (pintype "passive"))
      (node (ref "U4") (pin "1") (pinfunction "VCCA_1") (pintype "power_in"))
      (node (ref "U4") (pin "15") (pinfunction "DIR2_15") (pintype "input"))
      (node (ref "U4") (pin "7") (pinfunction "DIR4_7") (pintype "input"))
    )
    (net (code "34") (name "GND") (class "Default")
      (node (ref "C1") (pin "2") (pinfunction "2_2") (pintype "passive"))
      (node (ref "C10") (pin "2") (pinfunction "2_2") (pintype "passive"))
      (node (ref "C11") (pin "2") (pinfunction "2_2") (pintype "passive"))
      (node (ref "C12") (pin "2") (pinfunction "2_2") (pintype "passive"))
      (node (ref "C13") (pin "2") (pinfunction "2_2") (pintype "passive"))
      (node (ref "C14") (pin "1") (pinfunction "1_1") (pintype "passive"))
      (node (ref "C15") (pin "2") (pinfunction "2_2") (pintype "passive"))
      (node (ref "C18") (pin "1") (pinfunction "1_1") (pintype "passive"))
      (node (ref "C19") (pin "1") (pinfunction "1_1") (pintype "passive"))
      (node (ref "C2") (pin "2") (pinfunction "2_2") (pintype "passive"))
      (node (ref "C20") (pin "2") (pinfunction "2_2") (pintype "passive"))
      (node (ref "C21") (pin "1") (pinfunction "1_1") (pintype "passive"))
      (node (ref "C22") (pin "1") (pinfunction "1_1") (pintype "passive"))
      (node (ref "C23") (pin "1") (pinfunction "1_1") (pintype "passive"))
      (node (ref "C24") (pin "2") (pinfunction "2_2") (pintype "passive"))
      (node (ref "C25") (pin "1") (pinfunction "1_1") (pintype "passive"))
      (node (ref "C26") (pin "1") (pinfunction "1_1") (pintype "passive"))
      (node (ref "C27") (pin "2") (pinfunction "2_2") (pintype "passive"))
      (node (ref "C29") (pin "2") (pinfunction "2_2") (pintype "passive"))
      (node (ref "C3") (pin "2") (pinfunction "2_2") (pintype "passive"))
      (node (ref "C30") (pin "2") (pinfunction "2_2") (pintype "passive"))
      (node (ref "C31") (pin "2") (pinfunction "2_2") (pintype "passive"))
      (node (ref "C34") (pin "2") (pinfunction "2_2") (pintype "passive"))
      (node (ref "C36") (pin "2") (pinfunction "2_2") (pintype "passive"))
      (node (ref "C4") (pin "2") (pinfunction "2_2") (pintype "passive"))
      (node (ref "C5") (pin "2") (pinfunction "2_2") (pintype "passive"))
      (node (ref "C6") (pin "2") (pinfunction "2_2") (pintype "passive"))
      (node (ref "C7") (pin "2") (pinfunction "2_2") (pintype "passive"))
      (node (ref "C8") (pin "1") (pinfunction "1_1") (pintype "passive"))
      (node (ref "C9") (pin "2") (pinfunction "2_2") (pintype "passive"))
      (node (ref "D1") (pin "3") (pinfunction "GND_3") (pintype "power_in"))
      (node (ref "D1") (pin "EPAD") (pinfunction "GND_EPAD") (pintype "power_in"))
      (node (ref "D10") (pin "C") (pinfunction "Cathode_C") (pintype "passive"))
      (node (ref "D11") (pin "C") (pinfunction "Cathode_C") (pintype "passive"))
      (node (ref "D12") (pin "C") (pinfunction "Cathode_C") (pintype "passive"))
      (node (ref "D7") (pin "C") (pinfunction "Cathode_C") (pintype "passive"))
      (node (ref "D9") (pin "C") (pinfunction "Cathode_C") (pintype "passive"))
      (node (ref "ESIM") (pin "1") (pinfunction "GND_1") (pintype "power_in"))
      (node (ref "ESIM") (pin "EPAD") (pinfunction "GND_EPAD") (pintype "passive"))
      (node (ref "J1") (pin "2") (pinfunction "2_2") (pintype "power_in"))
      (node (ref "J3") (pin "1") (pinfunction "1_1") (pintype "passive"))
      (node (ref "J7") (pin "2") (pinfunction "2_2") (pintype "power_in"))
      (node (ref "J8") (pin "1") (pinfunction "ANT_1") (pintype "passive"))
      (node (ref "J8") (pin "2") (pinfunction "2_2") (pintype "power_in"))
      (node (ref "J9") (pin "2") (pinfunction "2_2") (pintype "power_in"))
      (node (ref "NO1") (pin "2") (pinfunction "2_2") (pintype "passive"))
      (node (ref "P1") (pin "C5") (pinfunction "GND_C5") (pintype "power_in"))
      (node (ref "P1") (pin "G1") (pinfunction "SHLDGND_G1") (pintype "power_in"))
      (node (ref "P1") (pin "G2") (pinfunction "SHLDGND_G2") (pintype "power_in"))
      (node (ref "P1") (pin "G3") (pinfunction "SHLDGND_G3") (pintype "power_in"))
      (node (ref "P1") (pin "G4") (pinfunction "SHLDGND_G4") (pintype "power_in"))
      (node (ref "Q10") (pin "1") (pinfunction "S1_1") (pintype "passive"))
      (node (ref "Q10") (pin "4") (pinfunction "S2_4") (pintype "passive"))
      (node (ref "Q15") (pin "1") (pinfunction "S1_1") (pintype "passive"))
      (node (ref "Q4") (pin "1") (pinfunction "S1_1") (pintype "passive"))
      (node (ref "Q4") (pin "4") (pinfunction "S2_4") (pintype "passive"))
      (node (ref "Q5") (pin "1") (pinfunction "S1_1") (pintype "passive"))
      (node (ref "R119") (pin "1") (pinfunction "1_1") (pintype "passive"))
      (node (ref "R120") (pin "1") (pinfunction "1_1") (pintype "passive"))
      (node (ref "R121") (pin "1") (pinfunction "1_1") (pintype "passive"))
      (node (ref "R16") (pin "2") (pinfunction "2_2") (pintype "passive"))
      (node (ref "R17") (pin "1") (pinfunction "1_1") (pintype "passive"))
      (node (ref "R19") (pin "2") (pinfunction "2_2") (pintype "passive"))
      (node (ref "R31") (pin "2") (pinfunction "2_2") (pintype "passive"))
      (node (ref "R34") (pin "2") (pinfunction "2_2") (pintype "passive"))
      (node (ref "R47") (pin "1") (pinfunction "1_1") (pintype "passive"))
      (node (ref "U1") (pin "1") (pinfunction "GND_1") (pintype "power_in"))
      (node (ref "U1") (pin "14") (pinfunction "GND_14") (pintype "power_in"))
      (node (ref "U1") (pin "20") (pinfunction "GND_20") (pintype "power_in"))
      (node (ref "U1") (pin "22") (pinfunction "GND_22") (pintype "power_in"))
      (node (ref "U1") (pin "3") (pinfunction "GND_3") (pintype "power_in"))
      (node (ref "U1") (pin "30") (pinfunction "GND_30") (pintype "power_in"))
      (node (ref "U1") (pin "32") (pinfunction "GND_32") (pintype "power_in"))
      (node (ref "U1") (pin "43") (pinfunction "GND_43") (pintype "power_in"))
      (node (ref "U1") (pin "5") (pinfunction "GND_5") (pintype "power_in"))
      (node (ref "U1") (pin "50") (pinfunction "GND_50") (pintype "power_in"))
      (node (ref "U1") (pin "54") (pinfunction "GND_54") (pintype "power_in"))
      (node (ref "U1") (pin "55") (pinfunction "GND_55") (pintype "power_in"))
      (node (ref "U1") (pin "57") (pinfunction "GND_57") (pintype "power_in"))
      (node (ref "U1") (pin "58") (pinfunction "GND_58") (pintype "power_in"))
      (node (ref "U1") (pin "59") (pinfunction "GND_59") (pintype "power_in"))
      (node (ref "U1") (pin "60") (pinfunction "GND_60") (pintype "power_in"))
      (node (ref "U1") (pin "61") (pinfunction "GND_61") (pintype "power_in"))
      (node (ref "U1") (pin "63") (pinfunction "GND_63") (pintype "power_in"))
      (node (ref "U1") (pin "64") (pinfunction "GND_64") (pintype "power_in"))
      (node (ref "U1") (pin "65") (pinfunction "GND_65") (pintype "passive"))
      (node (ref "U1") (pin "66") (pinfunction "GND_66") (pintype "passive"))
      (node (ref "U1") (pin "67") (pinfunction "GND_67") (pintype "passive"))
      (node (ref "U1") (pin "68") (pinfunction "GND_68") (pintype "passive"))
      (node (ref "U1") (pin "69") (pinfunction "GND_69") (pintype "passive"))
      (node (ref "U1") (pin "70") (pinfunction "GND_70") (pintype "passive"))
      (node (ref "U1") (pin "71") (pinfunction "GND_71") (pintype "passive"))
      (node (ref "U1") (pin "72") (pinfunction "GND_72") (pintype "passive"))
      (node (ref "U1") (pin "73") (pinfunction "GND_73") (pintype "passive"))
      (node (ref "U1") (pin "74") (pinfunction "GND_74") (pintype "passive"))
      (node (ref "U1") (pin "75") (pinfunction "GND_75") (pintype "passive"))
      (node (ref "U1") (pin "76") (pinfunction "GND_76") (pintype "passive"))
      (node (ref "U1") (pin "77") (pinfunction "GND_77") (pintype "passive"))
      (node (ref "U1") (pin "78") (pinfunction "GND_78") (pintype "passive"))
      (node (ref "U1") (pin "79") (pinfunction "GND_79") (pintype "passive"))
      (node (ref "U1") (pin "80") (pinfunction "GND_80") (pintype "passive"))
      (node (ref "U1") (pin "81") (pinfunction "GND_81") (pintype "passive"))
      (node (ref "U1") (pin "82") (pinfunction "GND_82") (pintype "passive"))
      (node (ref "U1") (pin "83") (pinfunction "GND_83") (pintype "passive"))
      (node (ref "U1") (pin "84") (pinfunction "GND_84") (pintype "passive"))
      (node (ref "U1") (pin "85") (pinfunction "GND_85") (pintype "passive"))
      (node (ref "U1") (pin "86") (pinfunction "GND_86") (pintype "passive"))
      (node (ref "U1") (pin "87") (pinfunction "GND_87") (pintype "passive"))
      (node (ref "U1") (pin "88") (pinfunction "GND_88") (pintype "passive"))
      (node (ref "U1") (pin "89") (pinfunction "GND_89") (pintype "passive"))
      (node (ref "U1") (pin "90") (pinfunction "GND_90") (pintype "passive"))
      (node (ref "U1") (pin "91") (pinfunction "GND_91") (pintype "passive"))
      (node (ref "U1") (pin "92") (pinfunction "GND_92") (pintype "passive"))
      (node (ref "U1") (pin "93") (pinfunction "GND_93") (pintype "passive"))
      (node (ref "U1") (pin "94") (pinfunction "GND_94") (pintype "passive"))
      (node (ref "U1") (pin "95") (pinfunction "GND_95") (pintype "passive"))
      (node (ref "U1") (pin "96") (pinfunction "GND_96") (pintype "passive"))
      (node (ref "U2") (pin "6") (pinfunction "GND_6") (pintype "power_in"))
      (node (ref "U4") (pin "10") (pinfunction "DIR3_10") (pintype "input"))
      (node (ref "U4") (pin "2") (pinfunction "DIR1_2") (pintype "input"))
      (node (ref "U4") (pin "8") (pinfunction "GND_8") (pintype "power_in"))
      (node (ref "U4") (pin "9") (pinfunction "~{OE}_9") (pintype "input"))
      (node (ref "U5") (pin "2") (pinfunction "DIR1_2") (pintype "input"))
      (node (ref "U5") (pin "7") (pinfunction "DIR4_7") (pintype "input"))
      (node (ref "U5") (pin "8") (pinfunction "GND_8") (pintype "power_in"))
      (node (ref "U5") (pin "9") (pinfunction "~{OE}_9") (pintype "input"))
      (node (ref "Z2") (pin "1") (pinfunction "1_1") (pintype "passive"))
      (node (ref "Z3") (pin "1") (pinfunction "1_1") (pintype "passive"))
      (node (ref "Z5") (pin "2") (pinfunction "2_2") (pintype "passive"))
      (node (ref "Z6") (pin "2") (pinfunction "2_2") (pintype "passive"))
    )
    (net (code "35") (name "MFF2_VSIM") (class "Default")
      (node (ref "C11") (pin "1") (pinfunction "1_1") (pintype "passive"))
      (node (ref "C9") (pin "1") (pinfunction "1_1") (pintype "passive"))
      (node (ref "ESIM") (pin "8") (pinfunction "VCC_8") (pintype "power_in"))
      (node (ref "U2") (pin "1") (pinfunction "1Y0_1") (pintype "bidirectional"))
    )
    (net (code "36") (name "NANO_VSIM") (class "Default")
      (node (ref "C2") (pin "1") (pinfunction "1_1") (pintype "passive"))
      (node (ref "C3") (pin "1") (pinfunction "1_1") (pintype "passive"))
      (node (ref "C4") (pin "1") (pinfunction "1_1") (pintype "passive"))
      (node (ref "D1") (pin "6") (pinfunction "Vcc_6") (pintype "power_in"))
      (node (ref "P1") (pin "C1") (pinfunction "VSIM_C1") (pintype "power_in"))
      (node (ref "U2") (pin "15") (pinfunction "1Y1_15") (pintype "bidirectional"))
    )
    (net (code "37") (name "Net-(A1-Pad1)") (class "Default")
      (node (ref "A1") (pin "1") (pinfunction "1_1") (pintype "passive"))
      (node (ref "Z1") (pin "2") (pinfunction "2_2") (pintype "passive"))
      (node (ref "Z2") (pin "2") (pinfunction "2_2") (pintype "passive"))
    )
    (net (code "38") (name "Net-(D7-Anode)") (class "Default")
      (node (ref "D7") (pin "A") (pinfunction "Anode_A") (pintype "passive"))
      (node (ref "R21") (pin "1") (pinfunction "1_1") (pintype "passive"))
    )
    (net (code "39") (name "Net-(D9-Anode)") (class "Default")
      (node (ref "D9") (pin "A") (pinfunction "Anode_A") (pintype "passive"))
      (node (ref "R23") (pin "1") (pinfunction "1_1") (pintype "passive"))
    )
    (net (code "40") (name "Net-(D10-Anode)") (class "Default")
      (node (ref "D10") (pin "A") (pinfunction "Anode_A") (pintype "passive"))
      (node (ref "R24") (pin "1") (pinfunction "1_1") (pintype "passive"))
    )
    (net (code "41") (name "Net-(D11-Anode)") (class "Default")
      (node (ref "D11") (pin "A") (pinfunction "Anode_A") (pintype "passive"))
      (node (ref "R28") (pin "1") (pinfunction "1_1") (pintype "passive"))
    )
    (net (code "42") (name "Net-(D12-Anode)") (class "Default")
      (node (ref "D12") (pin "A") (pinfunction "Anode_A") (pintype "passive"))
      (node (ref "R25") (pin "1") (pinfunction "1_1") (pintype "passive"))
    )
    (net (code "43") (name "Net-(FB1-Pad2)") (class "Default")
      (node (ref "FB1") (pin "2") (pinfunction "2_2") (pintype "passive"))
      (node (ref "U1") (pin "51") (pinfunction "VCC_51") (pintype "power_in"))
      (node (ref "U1") (pin "52") (pinfunction "VCC_52") (pintype "power_in"))
      (node (ref "U1") (pin "53") (pinfunction "VCC_53") (pintype "power_in"))
    )
    (net (code "44") (name "Net-(J1-ANT)") (class "Default")
      (node (ref "J1") (pin "1") (pinfunction "ANT_1") (pintype "passive"))
      (node (ref "R5") (pin "2") (pinfunction "2_2") (pintype "passive"))
      (node (ref "R7") (pin "2") (pinfunction "2_2") (pintype "passive"))
    )
    (net (code "45") (name "Net-(J9-ANT)") (class "Default")
      (node (ref "J9") (pin "1") (pinfunction "ANT_1") (pintype "passive"))
      (node (ref "R119") (pin "2") (pinfunction "2_2") (pintype "passive"))
      (node (ref "R120") (pin "2") (pinfunction "2_2") (pintype "passive"))
      (node (ref "R121") (pin "2") (pinfunction "2_2") (pintype "passive"))
    )
    (net (code "46") (name "Net-(NC2-Pad2)") (class "Default")
      (node (ref "NC2") (pin "2") (pinfunction "2_2") (pintype "passive"))
      (node (ref "R21") (pin "2") (pinfunction "2_2") (pintype "passive"))
    )
    (net (code "47") (name "Net-(Q4A-D1)") (class "Default")
      (node (ref "Q4") (pin "3") (pinfunction "D2_3") (pintype "passive"))
      (node (ref "Q4") (pin "6") (pinfunction "D1_6") (pintype "passive"))
      (node (ref "U1") (pin "18") (pinfunction "RESET_N_18") (pintype "input"))
    )
    (net (code "48") (name "Net-(Q4A-G1)") (class "Default")
      (node (ref "NC4") (pin "1") (pinfunction "1_1") (pintype "passive"))
      (node (ref "Q4") (pin "2") (pinfunction "G1_2") (pintype "passive"))
      (node (ref "R19") (pin "1") (pinfunction "1_1") (pintype "passive"))
    )
    (net (code "49") (name "Net-(Q5A-D1)") (class "Default")
      (node (ref "Q5") (pin "5") (pinfunction "G2_5") (pintype "passive"))
      (node (ref "Q5") (pin "6") (pinfunction "D1_6") (pintype "passive"))
      (node (ref "R20") (pin "2") (pinfunction "2_2") (pintype "passive"))
    )
    (net (code "50") (name "Net-(Q5B-D2)") (class "Default")
      (node (ref "Q5") (pin "3") (pinfunction "D2_3") (pintype "passive"))
      (node (ref "U1") (pin "33") (pinfunction "EXT_INT_33") (pintype "input"))
    )
    (net (code "51") (name "Net-(Q6A-D1)") (class "Default")
      (node (ref "Q6") (pin "6") (pinfunction "D1_6") (pintype "passive"))
      (node (ref "R23") (pin "2") (pinfunction "2_2") (pintype "passive"))
    )
    (net (code "52") (name "Net-(Q6B-D2)") (class "Default")
      (node (ref "Q6") (pin "3") (pinfunction "D2_3") (pintype "passive"))
      (node (ref "R24") (pin "2") (pinfunction "2_2") (pintype "passive"))
    )
    (net (code "53") (name "Net-(Q7A-D1)") (class "Default")
      (node (ref "Q7") (pin "6") (pinfunction "D1_6") (pintype "passive"))
      (node (ref "R25") (pin "2") (pinfunction "2_2") (pintype "passive"))
    )
    (net (code "54") (name "Net-(Q7B-D2)") (class "Default")
      (node (ref "Q7") (pin "3") (pinfunction "D2_3") (pintype "passive"))
      (node (ref "R28") (pin "2") (pinfunction "2_2") (pintype "passive"))
    )
    (net (code "55") (name "Net-(Q9-D)") (class "Default")
      (node (ref "C36") (pin "1") (pinfunction "1_1") (pintype "passive"))
      (node (ref "J3") (pin "3") (pinfunction "3_3") (pintype "passive"))
      (node (ref "NC2") (pin "1") (pinfunction "1_1") (pintype "passive"))
      (node (ref "NC6") (pin "2") (pinfunction "2_2") (pintype "passive"))
      (node (ref "Q9") (pin "3") (pinfunction "D_3") (pintype "passive"))
    )
    (net (code "56") (name "Net-(Q10A-D1)") (class "Default")
      (node (ref "NO1") (pin "1") (pinfunction "1_1") (pintype "passive"))
      (node (ref "Q10") (pin "6") (pinfunction "D1_6") (pintype "passive"))
      (node (ref "Q9") (pin "1") (pinfunction "G_1") (pintype "passive"))
      (node (ref "R32") (pin "1") (pinfunction "1_1") (pintype "passive"))
    )
    (net (code "57") (name "Net-(Q10B-D2)") (class "Default")
      (node (ref "Q10") (pin "3") (pinfunction "D2_3") (pintype "passive"))
      (node (ref "U1") (pin "15") (pinfunction "PWR_ON_15") (pintype "input"))
    )
    (net (code "58") (name "Net-(Q15A-D1)") (class "Default")
      (node (ref "Q15") (pin "5") (pinfunction "G2_5") (pintype "passive"))
      (node (ref "Q15") (pin "6") (pinfunction "D1_6") (pintype "passive"))
      (node (ref "R49") (pin "2") (pinfunction "2_2") (pintype "passive"))
    )
    (net (code "59") (name "Net-(Q15A-G1)") (class "Default")
      (node (ref "NO3") (pin "1") (pinfunction "1_1") (pintype "passive"))
      (node (ref "Q15") (pin "2") (pinfunction "G1_2") (pintype "passive"))
      (node (ref "R47") (pin "2") (pinfunction "2_2") (pintype "passive"))
    )
    (net (code "60") (name "Net-(Q15B-D2)") (class "Default")
      (node (ref "Q15") (pin "3") (pinfunction "D2_3") (pintype "passive"))
      (node (ref "U1") (pin "17") (pinfunction "VUSB_DET_17") (pintype "input"))
    )
    (net (code "61") (name "Net-(R6-Pad1)") (class "Default")
      (node (ref "R6") (pin "1") (pinfunction "1_1") (pintype "passive"))
      (node (ref "R7") (pin "1") (pinfunction "1_1") (pintype "passive"))
      (node (ref "Z4") (pin "2") (pinfunction "2_2") (pintype "passive"))
      (node (ref "Z6") (pin "1") (pinfunction "1_1") (pintype "passive"))
    )
    (net (code "62") (name "Net-(U1-ANT)") (class "Default")
      (node (ref "R5") (pin "1") (pinfunction "1_1") (pintype "passive"))
      (node (ref "R6") (pin "2") (pinfunction "2_2") (pintype "passive"))
      (node (ref "U1") (pin "56") (pinfunction "ANT_56") (pintype "bidirectional"))
    )
    (net (code "63") (name "Net-(U1-CTS)") (class "Default")
      (node (ref "U1") (pin "11") (pinfunction "CTS_11") (pintype "output"))
      (node (ref "U4") (pin "12") (pinfunction "B3_12") (pintype "bidirectional"))
    )
    (net (code "64") (name "Net-(U1-DCD)") (class "Default")
      (node (ref "U1") (pin "8") (pinfunction "DCD_8") (pintype "output"))
      (node (ref "U5") (pin "5") (pinfunction "A3_5") (pintype "bidirectional"))
    )
    (net (code "65") (name "Net-(U1-DSR)") (class "Default")
      (node (ref "U1") (pin "6") (pinfunction "DSR_6") (pintype "output"))
      (node (ref "U5") (pin "3") (pinfunction "A1_3") (pintype "bidirectional"))
    )
    (net (code "66") (name "Net-(U1-DTR)") (class "Default")
      (node (ref "U1") (pin "9") (pinfunction "DTR_9") (pintype "input"))
      (node (ref "U5") (pin "6") (pinfunction "A4_6") (pintype "bidirectional"))
    )
    (net (code "67") (name "Net-(U1-RI)") (class "Default")
      (node (ref "U1") (pin "7") (pinfunction "RI_7") (pintype "output"))
      (node (ref "U5") (pin "4") (pinfunction "A2_4") (pintype "bidirectional"))
    )
    (net (code "68") (name "Net-(U1-RTS)") (class "Default")
      (node (ref "U1") (pin "10") (pinfunction "RTS_10") (pintype "input"))
      (node (ref "U4") (pin "11") (pinfunction "B4_11") (pintype "bidirectional"))
    )
    (net (code "69") (name "Net-(U1-RXD)") (class "Default")
      (node (ref "U1") (pin "13") (pinfunction "RXD_13") (pintype "output"))
      (node (ref "U4") (pin "14") (pinfunction "B1_14") (pintype "bidirectional"))
    )
    (net (code "70") (name "Net-(U1-TXD)") (class "Default")
      (node (ref "U1") (pin "12") (pinfunction "TXD_12") (pintype "input"))
      (node (ref "U4") (pin "13") (pinfunction "B2_13") (pintype "bidirectional"))
    )
    (net (code "71") (name "Net-(U4-A3)") (class "Default")
      (node (ref "TP20") (pin "1") (pintype "passive"))
      (node (ref "U4") (pin "5") (pinfunction "A3_5") (pintype "bidirectional"))
    )
    (net (code "72") (name "Net-(U4-A4)") (class "Default")
      (node (ref "TP21") (pin "1") (pintype "passive"))
      (node (ref "U4") (pin "6") (pinfunction "A4_6") (pintype "bidirectional"))
    )
    (net (code "73") (name "Net-(U5-B1)") (class "Default")
      (node (ref "TP22") (pin "1") (pintype "passive"))
      (node (ref "U5") (pin "14") (pinfunction "B1_14") (pintype "bidirectional"))
    )
    (net (code "74") (name "Net-(U5-B2)") (class "Default")
      (node (ref "TP17") (pin "1") (pintype "passive"))
      (node (ref "U5") (pin "13") (pinfunction "B2_13") (pintype "bidirectional"))
    )
    (net (code "75") (name "Net-(Z1-Pad1)") (class "Default")
      (node (ref "Z1") (pin "1") (pinfunction "1_1") (pintype "passive"))
      (node (ref "Z3") (pin "2") (pinfunction "2_2") (pintype "passive"))
      (node (ref "Z4") (pin "1") (pinfunction "1_1") (pintype "passive"))
      (node (ref "Z5") (pin "1") (pinfunction "1_1") (pintype "passive"))
    )
    (net (code "76") (name "SARA_1V8") (class "Default")
      (node (ref "C14") (pin "2") (pinfunction "2_2") (pintype "passive"))
      (node (ref "C15") (pin "1") (pinfunction "1_1") (pintype "passive"))
      (node (ref "C18") (pin "2") (pinfunction "2_2") (pintype "passive"))
      (node (ref "C19") (pin "2") (pinfunction "2_2") (pintype "passive"))
      (node (ref "C8") (pin "2") (pinfunction "2_2") (pintype "passive"))
      (node (ref "NO3") (pin "2") (pinfunction "2_2") (pintype "passive"))
      (node (ref "Q5") (pin "4") (pinfunction "S2_4") (pintype "passive"))
      (node (ref "R1") (pin "2") (pinfunction "2_2") (pintype "passive"))
      (node (ref "R20") (pin "1") (pinfunction "1_1") (pintype "passive"))
      (node (ref "TP10") (pin "1") (pintype "passive"))
      (node (ref "U1") (pin "4") (pinfunction "V_INT_4") (pintype "output"))
      (node (ref "U4") (pin "16") (pinfunction "VCCB_16") (pintype "power_in"))
      (node (ref "U5") (pin "1") (pinfunction "VCCA_1") (pintype "power_in"))
      (node (ref "U5") (pin "10") (pinfunction "DIR3_10") (pintype "input"))
      (node (ref "U5") (pin "15") (pinfunction "DIR2_15") (pintype "input"))
    )
    (net (code "77") (name "SARA_VCC_IN") (class "Default")
      (node (ref "C13") (pin "1") (pinfunction "1_1") (pintype "passive"))
      (node (ref "C23") (pin "2") (pinfunction "2_2") (pintype "passive"))
      (node (ref "C24") (pin "1") (pinfunction "1_1") (pintype "passive"))
      (node (ref "C25") (pin "2") (pinfunction "2_2") (pintype "passive"))
      (node (ref "C26") (pin "2") (pinfunction "2_2") (pintype "passive"))
      (node (ref "C29") (pin "1") (pinfunction "1_1") (pintype "passive"))
      (node (ref "C30") (pin "1") (pinfunction "1_1") (pintype "passive"))
      (node (ref "C31") (pin "1") (pinfunction "1_1") (pintype "passive"))
      (node (ref "C34") (pin "1") (pinfunction "1_1") (pintype "passive"))
      (node (ref "FB1") (pin "1") (pinfunction "1_1") (pintype "passive"))
      (node (ref "J3") (pin "2") (pinfunction "2_2") (pintype "passive"))
      (node (ref "NC6") (pin "1") (pinfunction "1_1") (pintype "passive"))
      (node (ref "TP11") (pin "1") (pintype "passive"))
      (node (ref "U2") (pin "14") (pinfunction "VCC_14") (pintype "power_in"))
    )
    (net (code "78") (name "VBUS") (class "Default")
      (node (ref "Q15") (pin "4") (pinfunction "S2_4") (pintype "passive"))
      (node (ref "R49") (pin "1") (pinfunction "1_1") (pintype "passive"))
    )
    (net (code "79") (name "VSIM") (class "Default")
      (node (ref "TP1") (pin "1") (pintype "passive"))
      (node (ref "U1") (pin "41") (pinfunction "VSIM_41") (pintype "output"))
      (node (ref "U2") (pin "16") (pinfunction "1Z_16") (pintype "bidirectional"))
    )
    (net (code "80") (name "V_BAT") (class "Default")
      (node (ref "Q9") (pin "2") (pinfunction "S_2") (pintype "passive"))
      (node (ref "R32") (pin "2") (pinfunction "2_2") (pintype "passive"))
    )
    (net (code "81") (name "unconnected-(D1-NC-Pad5)") (class "Default")
      (node (ref "D1") (pin "5") (pinfunction "NC_5") (pintype "passive+no_connect"))
    )
    (net (code "82") (name "unconnected-(ESIM-NC-Pad4)") (class "Default")
      (node (ref "ESIM") (pin "4") (pinfunction "NC_4") (pintype "passive+no_connect"))
    )
    (net (code "83") (name "unconnected-(ESIM-NC-Pad5)") (class "Default")
      (node (ref "ESIM") (pin "5") (pinfunction "NC_5") (pintype "passive+no_connect"))
    )
    (net (code "84") (name "unconnected-(ESIM-VPP-Pad2)") (class "Default")
      (node (ref "ESIM") (pin "2") (pinfunction "VPP_2") (pintype "bidirectional+no_connect"))
    )
    (net (code "85") (name "unconnected-(P1-VPP{slash}NC-PadC6)") (class "Default")
      (node (ref "P1") (pin "C6") (pinfunction "VPP/NC_C6") (pintype "bidirectional+no_connect"))
    )
    (net (code "86") (name "unconnected-(U1-ANT_DET-Pad62)") (class "Default")
      (node (ref "U1") (pin "62") (pinfunction "ANT_DET_62") (pintype "input+no_connect"))
    )
    (net (code "87") (name "unconnected-(U1-ANT_GNSS-Pad31)") (class "Default")
      (node (ref "U1") (pin "31") (pinfunction "ANT_GNSS_31") (pintype "input+no_connect"))
    )
    (net (code "88") (name "unconnected-(U1-GND-Pad21)") (class "Default")
      (node (ref "U1") (pin "21") (pinfunction "GND_21") (pintype "power_in+no_connect"))
    )
    (net (code "89") (name "unconnected-(U1-GPIO1-Pad16)") (class "Default")
      (node (ref "U1") (pin "16") (pinfunction "GPIO1_16") (pintype "bidirectional+no_connect"))
    )
    (net (code "90") (name "unconnected-(U1-GPIO3-Pad24)") (class "Default")
      (node (ref "U1") (pin "24") (pinfunction "GPIO3_24") (pintype "bidirectional+no_connect"))
    )
    (net (code "91") (name "unconnected-(U1-GPIO6-Pad19)") (class "Default")
      (node (ref "U1") (pin "19") (pinfunction "GPIO6_19") (pintype "bidirectional+no_connect"))
    )
    (net (code "92") (name "unconnected-(U1-I2S_CLK-Pad36)") (class "Default")
      (node (ref "U1") (pin "36") (pinfunction "I2S_CLK_36") (pintype "output+no_connect"))
    )
    (net (code "93") (name "unconnected-(U1-I2S_RXD-Pad37)") (class "Default")
      (node (ref "U1") (pin "37") (pinfunction "I2S_RXD_37") (pintype "input+no_connect"))
    )
    (net (code "94") (name "unconnected-(U1-I2S_TXD-Pad35)") (class "Default")
      (node (ref "U1") (pin "35") (pinfunction "I2S_TXD_35") (pintype "output+no_connect"))
    )
    (net (code "95") (name "unconnected-(U1-I2S_WA-Pad34)") (class "Default")
      (node (ref "U1") (pin "34") (pinfunction "I2S_WA_34") (pintype "output+no_connect"))
    )
    (net (code "96") (name "unconnected-(U1-RSVD-Pad2)") (class "Default")
      (node (ref "U1") (pin "2") (pinfunction "RSVD_2") (pintype "passive+no_connect"))
    )
    (net (code "97") (name "unconnected-(U1-SDIO_CLK-Pad45)") (class "Default")
      (node (ref "U1") (pin "45") (pinfunction "SDIO_CLK_45") (pintype "output+no_connect"))
    )
    (net (code "98") (name "unconnected-(U1-SDIO_D0{slash}SPI_MOSI-Pad47)") (class "Default")
      (node (ref "U1") (pin "47") (pinfunction "SDIO_D0/SPI_MOSI_47") (pintype "bidirectional+no_connect"))
    )
    (net (code "99") (name "unconnected-(U1-SDIO_D1{slash}SPI_MISO-Pad49)") (class "Default")
      (node (ref "U1") (pin "49") (pinfunction "SDIO_D1/SPI_MISO_49") (pintype "bidirectional+no_connect"))
    )
    (net (code "100") (name "unconnected-(U1-SDIO_D2{slash}SPI_CLK-Pad44)") (class "Default")
      (node (ref "U1") (pin "44") (pinfunction "SDIO_D2/SPI_CLK_44") (pintype "bidirectional+no_connect"))
    )
    (net (code "101") (name "unconnected-(U1-SDIO_D3{slash}SPI_CS-Pad48)") (class "Default")
      (node (ref "U1") (pin "48") (pinfunction "SDIO_D3/SPI_CS_48") (pintype "bidirectional+no_connect"))
    )
    (net (code "102") (name "unconnected-(U2-NC-Pad10)") (class "Default")
      (node (ref "U2") (pin "10") (pinfunction "NC_10") (pintype "passive+no_connect"))
    )
  )
)
